# Nutaq_Adaptor2.net
KiCad netlist of a schematic drawn in Altium Designer
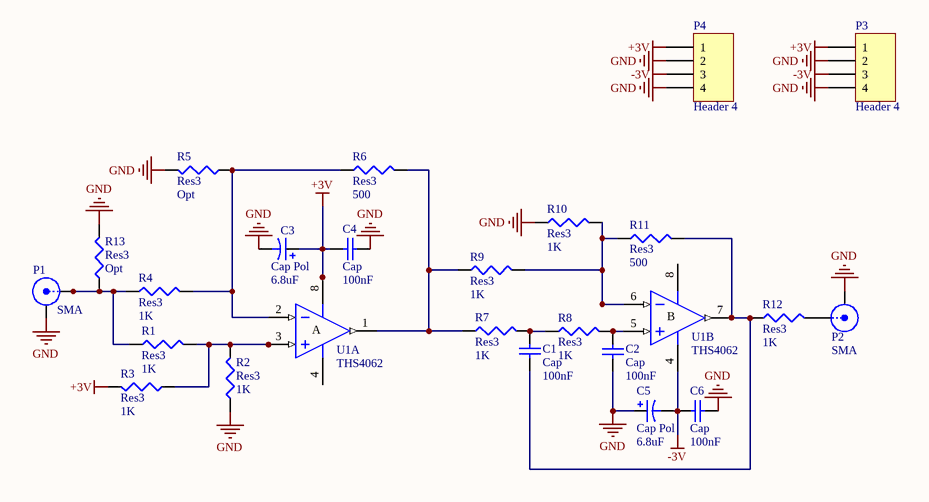
[diagram p0: Nutaq_Adaptor2.SchDoc]

(export (version "E")
  (design (tool "Eeschema 10.0.6"))
  (components
    (comp (ref "C1")
      (value "Cap")
      (footprint "1608[0603]")
      (description "Capacitor (Semiconductor SIM Model)")
      (fields (field (name "ALTIUM_VALUE") "100nF") (field (name "PUBLISHER") "Altium Limited"))
      (libsource (lib "Miscellaneous Devices") (part "Cap Semi"))
    )
    (comp (ref "C2")
      (value "Cap")
      (footprint "1608[0603]")
      (description "Capacitor (Semiconductor SIM Model)")
      (fields (field (name "ALTIUM_VALUE") "100nF") (field (name "PUBLISHER") "Altium Limited"))
      (libsource (lib "Miscellaneous Devices") (part "Cap Semi"))
    )
    (comp (ref "C3")
      (value "Cap Pol")
      (footprint "1608[0603]")
      (description "Polarized Capacitor (Surface Mount)")
      (fields (field (name "ALTIUM_VALUE") "6.8uF") (field (name "PUBLISHER") "Altium Limited"))
      (libsource (lib "Miscellaneous Devices") (part "Cap Pol3"))
    )
    (comp (ref "C4")
      (value "Cap")
      (footprint "1608[0603]")
      (description "Capacitor (Semiconductor SIM Model)")
      (fields (field (name "ALTIUM_VALUE") "100nF") (field (name "PUBLISHER") "Altium Limited"))
      (libsource (lib "Miscellaneous Devices") (part "Cap Semi"))
    )
    (comp (ref "C5")
      (value "Cap Pol")
      (footprint "1608[0603]")
      (description "Polarized Capacitor (Surface Mount)")
      (fields (field (name "ALTIUM_VALUE") "6.8uF") (field (name "PUBLISHER") "Altium Limited"))
      (libsource (lib "Miscellaneous Devices") (part "Cap Pol3"))
    )
    (comp (ref "C6")
      (value "Cap")
      (footprint "1608[0603]")
      (description "Capacitor (Semiconductor SIM Model)")
      (fields (field (name "ALTIUM_VALUE") "100nF") (field (name "PUBLISHER") "Altium Limited"))
      (libsource (lib "Miscellaneous Devices") (part "Cap Semi"))
    )
    (comp (ref "P1")
      (value "SMA")
      (footprint "SMB_V-RJ45")
      (description "SMB Straight Connector")
      (fields (field (name "PUBLISHER") "Altium Limited"))
      (libsource (lib "Miscellaneous Connectors") (part "SMB"))
    )
    (comp (ref "P2")
      (value "SMA")
      (footprint "SMB_V-RJ45")
      (description "SMB Straight Connector")
      (fields (field (name "PUBLISHER") "Altium Limited"))
      (libsource (lib "Miscellaneous Connectors") (part "SMB"))
    )
    (comp (ref "P3")
      (value "Header 4")
      (footprint "HDR1X4")
      (description "Header, 4-Pin")
      (fields (field (name "PUBLISHER") "Altium Limited"))
      (libsource (lib "Miscellaneous Connectors") (part "Header 4"))
    )
    (comp (ref "P4")
      (value "Header 4")
      (footprint "HDR1X4")
      (description "Header, 4-Pin")
      (fields (field (name "PUBLISHER") "Altium Limited"))
      (libsource (lib "Miscellaneous Connectors") (part "Header 4"))
    )
    (comp (ref "R1")
      (value "Res3")
      (footprint "J1-0603")
      (description "Resistor")
      (fields (field (name "ALTIUM_VALUE") "1K") (field (name "PUBLISHER") "Altium Limited"))
      (libsource (lib "Miscellaneous Devices") (part "Res3"))
    )
    (comp (ref "R2")
      (value "Res3")
      (footprint "J1-0603")
      (description "Resistor")
      (fields (field (name "ALTIUM_VALUE") "1K") (field (name "PUBLISHER") "Altium Limited"))
      (libsource (lib "Miscellaneous Devices") (part "Res3"))
    )
    (comp (ref "R3")
      (value "Res3")
      (footprint "J1-0603")
      (description "Resistor")
      (fields (field (name "ALTIUM_VALUE") "1K") (field (name "PUBLISHER") "Altium Limited"))
      (libsource (lib "Miscellaneous Devices") (part "Res3"))
    )
    (comp (ref "R4")
      (value "Res3")
      (footprint "J1-0603")
      (description "Resistor")
      (fields (field (name "ALTIUM_VALUE") "1K") (field (name "PUBLISHER") "Altium Limited"))
      (libsource (lib "Miscellaneous Devices") (part "Res3"))
    )
    (comp (ref "R5")
      (value "Res3")
      (footprint "J1-0603")
      (description "Resistor")
      (fields (field (name "ALTIUM_VALUE") "Opt") (field (name "PUBLISHER") "Altium Limited"))
      (libsource (lib "Miscellaneous Devices") (part "Res3"))
    )
    (comp (ref "R6")
      (value "Res3")
      (footprint "J1-0603")
      (description "Resistor")
      (fields (field (name "ALTIUM_VALUE") "500") (field (name "PUBLISHER") "Altium Limited"))
      (libsource (lib "Miscellaneous Devices") (part "Res3"))
    )
    (comp (ref "R7")
      (value "Res3")
      (footprint "J1-0603")
      (description "Resistor")
      (fields (field (name "ALTIUM_VALUE") "1K") (field (name "PUBLISHER") "Altium Limited"))
      (libsource (lib "Miscellaneous Devices") (part "Res3"))
    )
    (comp (ref "R8")
      (value "Res3")
      (footprint "J1-0603")
      (description "Resistor")
      (fields (field (name "ALTIUM_VALUE") "1K") (field (name "PUBLISHER") "Altium Limited"))
      (libsource (lib "Miscellaneous Devices") (part "Res3"))
    )
    (comp (ref "R9")
      (value "Res3")
      (footprint "J1-0603")
      (description "Resistor")
      (fields (field (name "ALTIUM_VALUE") "1K") (field (name "PUBLISHER") "Altium Limited"))
      (libsource (lib "Miscellaneous Devices") (part "Res3"))
    )
    (comp (ref "R10")
      (value "Res3")
      (footprint "J1-0603")
      (description "Resistor")
      (fields (field (name "ALTIUM_VALUE") "1K") (field (name "PUBLISHER") "Altium Limited"))
      (libsource (lib "Miscellaneous Devices") (part "Res3"))
    )
    (comp (ref "R11")
      (value "Res3")
      (footprint "J1-0603")
      (description "Resistor")
      (fields (field (name "ALTIUM_VALUE") "500") (field (name "PUBLISHER") "Altium Limited"))
      (libsource (lib "Miscellaneous Devices") (part "Res3"))
    )
    (comp (ref "R12")
      (value "Res3")
      (footprint "J1-0603")
      (description "Resistor")
      (fields (field (name "ALTIUM_VALUE") "1K") (field (name "PUBLISHER") "Altium Limited"))
      (libsource (lib "Miscellaneous Devices") (part "Res3"))
    )
    (comp (ref "R13")
      (value "Res3")
      (footprint "J1-0603")
      (description "Resistor")
      (fields (field (name "ALTIUM_VALUE") "Opt") (field (name "PUBLISHER") "Altium Limited"))
      (libsource (lib "Miscellaneous Devices") (part "Res3"))
    )
    (comp (ref "U1")
      (value "THS4062")
      (footprint "SO-8_M")
      (description "Dual 600MHz, 50mW Current Feedback Amplifier")
      (fields (field (name "PUBLISHER") "Altium Limited"))
      (libsource (lib "AD Operational Amplifier") (part "AD8002AR"))
    )
  )
  (nets
    (net (code "1") (name "+3V") (class "Default")
      (node (ref "C3") (pin "1") (pinfunction "1_1") (pintype "passive"))
      (node (ref "C4") (pin "1") (pinfunction "1_1") (pintype "passive"))
      (node (ref "P3") (pin "1") (pinfunction "1_1") (pintype "passive"))
      (node (ref "P4") (pin "1") (pinfunction "1_1") (pintype "passive"))
      (node (ref "R3") (pin "2") (pinfunction "2_2") (pintype "passive"))
      (node (ref "U1") (pin "8") (pinfunction "V+_8") (pintype "power_in"))
    )
    (net (code "2") (name "-3V") (class "Default")
      (node (ref "C5") (pin "2") (pinfunction "2_2") (pintype "passive"))
      (node (ref "C6") (pin "1") (pinfunction "1_1") (pintype "passive"))
      (node (ref "P3") (pin "3") (pinfunction "3_3") (pintype "passive"))
      (node (ref "P4") (pin "3") (pinfunction "3_3") (pintype "passive"))
      (node (ref "U1") (pin "4") (pinfunction "V-_4") (pintype "power_in"))
    )
    (net (code "3") (name "GND") (class "Default")
      (node (ref "C2") (pin "2") (pinfunction "2_2") (pintype "passive"))
      (node (ref "C3") (pin "2") (pinfunction "2_2") (pintype "passive"))
      (node (ref "C4") (pin "2") (pinfunction "2_2") (pintype "passive"))
      (node (ref "C5") (pin "1") (pinfunction "1_1") (pintype "passive"))
      (node (ref "C6") (pin "2") (pinfunction "2_2") (pintype "passive"))
      (node (ref "P1") (pin "2") (pinfunction "Y_2") (pintype "passive"))
      (node (ref "P2") (pin "2") (pinfunction "Y_2") (pintype "passive"))
      (node (ref "P3") (pin "2") (pinfunction "2_2") (pintype "passive"))
      (node (ref "P3") (pin "4") (pinfunction "4_4") (pintype "passive"))
      (node (ref "P4") (pin "2") (pinfunction "2_2") (pintype "passive"))
      (node (ref "P4") (pin "4") (pinfunction "4_4") (pintype "passive"))
      (node (ref "R10") (pin "1") (pinfunction "1_1") (pintype "passive"))
      (node (ref "R13") (pin "2") (pinfunction "2_2") (pintype "passive"))
      (node (ref "R2") (pin "1") (pinfunction "1_1") (pintype "passive"))
      (node (ref "R5") (pin "2") (pinfunction "2_2") (pintype "passive"))
    )
    (net (code "4") (name "Net-(C1-Pad1)") (class "Default")
      (node (ref "C1") (pin "1") (pinfunction "1_1") (pintype "passive"))
      (node (ref "R7") (pin "2") (pinfunction "2_2") (pintype "passive"))
      (node (ref "R8") (pin "1") (pinfunction "1_1") (pintype "passive"))
    )
    (net (code "5") (name "Net-(P1-X)") (class "Default")
      (node (ref "P1") (pin "1") (pinfunction "X_1") (pintype "passive"))
      (node (ref "R1") (pin "1") (pinfunction "1_1") (pintype "passive"))
      (node (ref "R13") (pin "1") (pinfunction "1_1") (pintype "passive"))
      (node (ref "R4") (pin "1") (pinfunction "1_1") (pintype "passive"))
    )
    (net (code "6") (name "Net-(P2-X)") (class "Default")
      (node (ref "P2") (pin "1") (pinfunction "X_1") (pintype "passive"))
      (node (ref "R12") (pin "2") (pinfunction "2_2") (pintype "passive"))
    )
    (net (code "7") (name "Net-(U1A-IN+)") (class "Default")
      (node (ref "R1") (pin "2") (pinfunction "2_2") (pintype "passive"))
      (node (ref "R2") (pin "2") (pinfunction "2_2") (pintype "passive"))
      (node (ref "R3") (pin "1") (pinfunction "1_1") (pintype "passive"))
      (node (ref "U1") (pin "3") (pinfunction "IN+_3") (pintype "input"))
    )
    (net (code "8") (name "Net-(U1A-IN-)") (class "Default")
      (node (ref "R4") (pin "2") (pinfunction "2_2") (pintype "passive"))
      (node (ref "R5") (pin "1") (pinfunction "1_1") (pintype "passive"))
      (node (ref "R6") (pin "1") (pinfunction "1_1") (pintype "passive"))
      (node (ref "U1") (pin "2") (pinfunction "IN-_2") (pintype "input"))
    )
    (net (code "9") (name "Net-(U1A-OUT)") (class "Default")
      (node (ref "R6") (pin "2") (pinfunction "2_2") (pintype "passive"))
      (node (ref "R7") (pin "1") (pinfunction "1_1") (pintype "passive"))
      (node (ref "R9") (pin "1") (pinfunction "1_1") (pintype "passive"))
      (node (ref "U1") (pin "1") (pinfunction "OUT_1") (pintype "output"))
    )
    (net (code "10") (name "Net-(U1B-IN+)") (class "Default")
      (node (ref "C2") (pin "1") (pinfunction "1_1") (pintype "passive"))
      (node (ref "R8") (pin "2") (pinfunction "2_2") (pintype "passive"))
      (node (ref "U1") (pin "5") (pinfunction "IN+_5") (pintype "input"))
    )
    (net (code "11") (name "Net-(U1B-IN-)") (class "Default")
      (node (ref "R10") (pin "2") (pinfunction "2_2") (pintype "passive"))
      (node (ref "R11") (pin "1") (pinfunction "1_1") (pintype "passive"))
      (node (ref "R9") (pin "2") (pinfunction "2_2") (pintype "passive"))
      (node (ref "U1") (pin "6") (pinfunction "IN-_6") (pintype "input"))
    )
    (net (code "12") (name "Net-(U1B-OUT)") (class "Default")
      (node (ref "C1") (pin "2") (pinfunction "2_2") (pintype "passive"))
      (node (ref "R11") (pin "2") (pinfunction "2_2") (pintype "passive"))
      (node (ref "R12") (pin "1") (pinfunction "1_1") (pintype "passive"))
      (node (ref "U1") (pin "7") (pinfunction "OUT_7") (pintype "output"))
    )
    (net (code "13") (name "unconnected-(U1A-V--Pad4)") (class "Default")
      (node (ref "U1") (pin "4") (pinfunction "V-_4") (pintype "power_in"))
    )
    (net (code "14") (name "unconnected-(U1B-V+-Pad8)") (class "Default")
      (node (ref "U1") (pin "8") (pinfunction "V+_8") (pintype "power_in"))
    )
  )
)
